# JTAG.net
KiCad netlist of a schematic drawn in Altium Designer
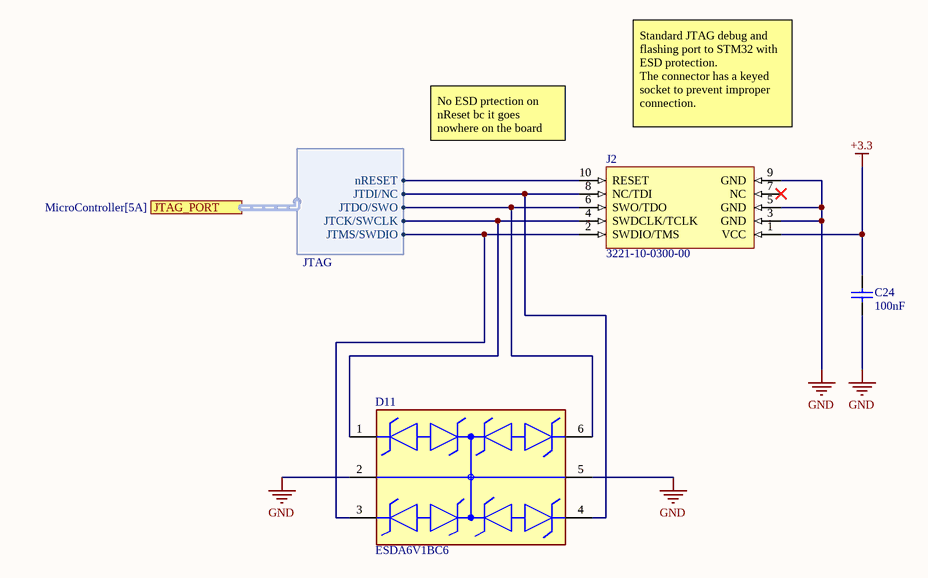
[diagram p0: JTAG.SchDoc]

(export (version "E")
  (design (tool "Eeschema 10.0.6"))
  (components
    (comp (ref "C24")
      (value "100nF")
      (footprint "CAPC1608X90X40ML10T20")
      (description "Chip Capacitor, 0.1uF, +/- 10%, 50 V, 0603 (1608 Metric)")
      (fields (field (name "TOLERANCE") "10%") (field (name "Comment") "Capacitor 0.1uF +/-10% 50 V 0603"))
      (libsource (lib "University of Minnesota - Solar Vehicle Project") (part "Cap"))
    )
    (comp (ref "D11")
      (value "ESDA6V1BC6")
      (footprint "FP-SOT23-6L-IPC_A")
      (description "Trans Voltage Suppressor Diode, 80W, 5V V(RWM), Bidirectional, 4 Element, Silicon")
      (libsource (lib "University of Minnesota - Solar Vehicle Project") (part "3fc8afaed3c8ed0e97b36f4d4f9a65f"))
    )
    (comp (ref "J2")
      (value "3221-10-0300-00")
      (footprint "3221-10-0300-00-Footprint-1")
      (description "JTAG STLINK CONN HEADER SMD 10POS 1.27MM")
      (libsource (lib "University of Minnesota - Solar Vehicle Project") (part "3221-10-0300-00-Symbol-1"))
    )
  )
  (nets
    (net (code "2") (name "+3.3") (class "Default")
      (node (ref "C24") (pin "2") (pinfunction "2_2") (pintype "passive"))
      (node (ref "J2") (pin "1") (pinfunction "VCC_1") (pintype "input"))
    )
    (net (code "3") (name "/JTCK{slash}SWCLK") (class "Default")
      (node (ref "D11") (pin "1") (pinfunction "1_1") (pintype "passive"))
      (node (ref "J2") (pin "4") (pinfunction "SWDCLK/TCLK_4") (pintype "input"))
    )
    (net (code "4") (name "/JTDI{slash}NC") (class "Default")
      (node (ref "D11") (pin "4") (pinfunction "4_4") (pintype "passive"))
      (node (ref "J2") (pin "8") (pinfunction "NC/TDI_8") (pintype "input"))
    )
    (net (code "5") (name "/JTDO{slash}SWO") (class "Default")
      (node (ref "D11") (pin "6") (pinfunction "6_6") (pintype "passive"))
      (node (ref "J2") (pin "6") (pinfunction "SWO/TDO_6") (pintype "input"))
    )
    (net (code "6") (name "/JTMS{slash}SWDIO") (class "Default")
      (node (ref "D11") (pin "3") (pinfunction "3_3") (pintype "passive"))
      (node (ref "J2") (pin "2") (pinfunction "SWDIO/TMS_2") (pintype "input"))
    )
    (net (code "7") (name "/nRESET") (class "Default")
      (node (ref "J2") (pin "10") (pinfunction "RESET_10") (pintype "input"))
    )
    (net (code "9") (name "GND") (class "Default")
      (node (ref "C24") (pin "1") (pinfunction "1_1") (pintype "passive"))
      (node (ref "D11") (pin "2") (pinfunction "2_2") (pintype "passive"))
      (node (ref "D11") (pin "5") (pinfunction "5_5") (pintype "passive"))
      (node (ref "J2") (pin "3") (pinfunction "GND_3") (pintype "input"))
      (node (ref "J2") (pin "5") (pinfunction "GND_5") (pintype "input"))
      (node (ref "J2") (pin "9") (pinfunction "GND_9") (pintype "input"))
    )
    (net (code "10") (name "unconnected-(J2-NC-Pad7)") (class "Default")
      (node (ref "J2") (pin "7") (pinfunction "NC_7") (pintype "input+no_connect"))
    )
  )
)
